# akabeacon_square_type1_MDBT40.net
KiCad netlist of a schematic drawn in EAGLE
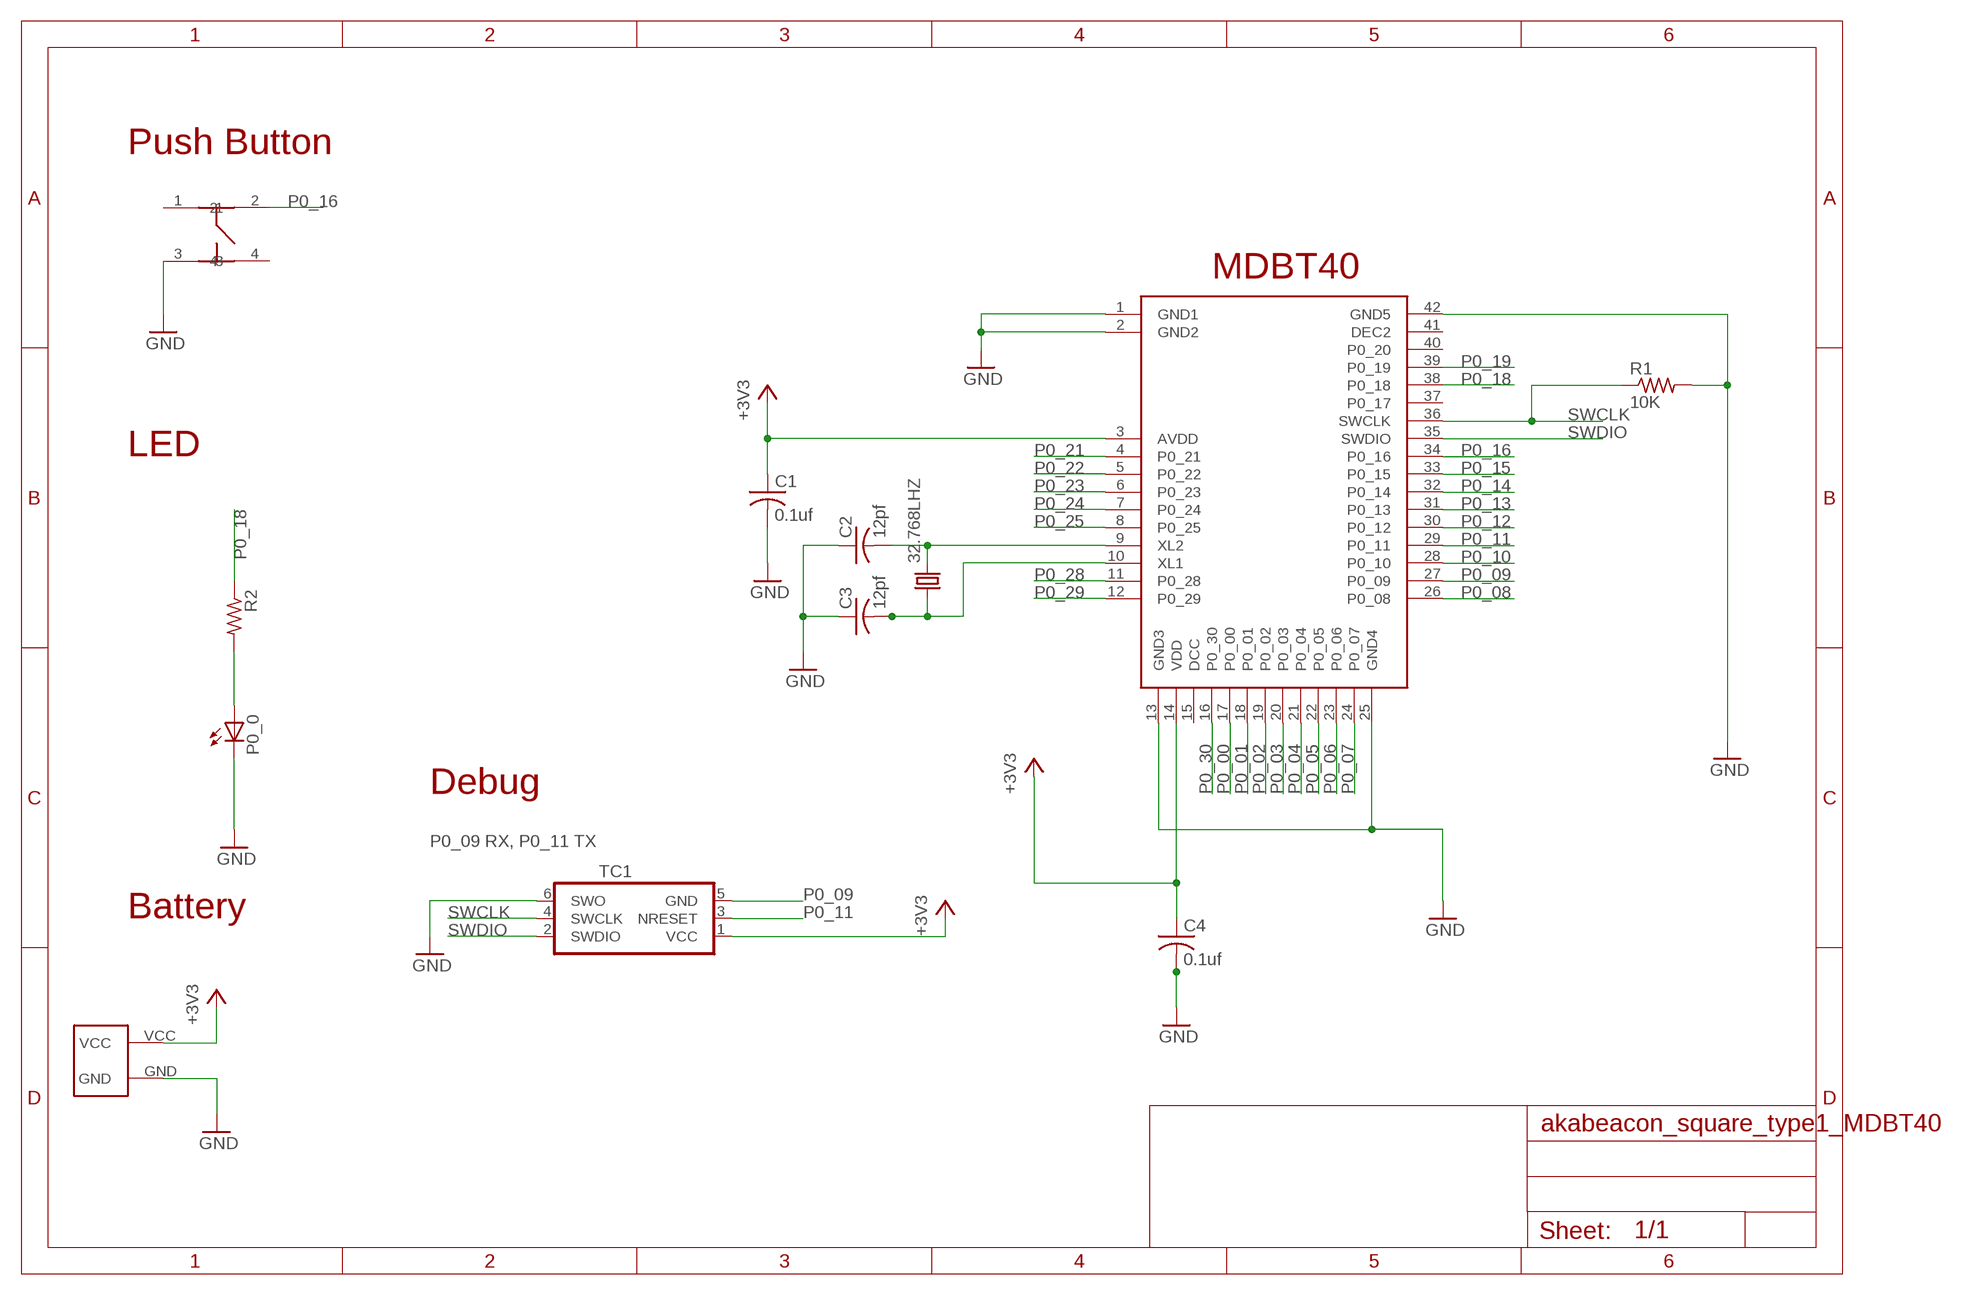
[diagram p0: schematic, sheet 1]

(export (version "E")
  (design (tool "Eeschema 10.0.6"))
  (components
    (comp (ref "32.768LHZ")
      (value "FC-12M")
      (footprint "eagle-import:FC-12M")
      (libsource (lib "eagle-import") (part "FC-12M"))
    )
    (comp (ref "C1")
      (value "0.1uf")
      (footprint "eagle-import:C0603")
      (libsource (lib "eagle-import") (part "C-USC0603"))
    )
    (comp (ref "C2")
      (value "12pf")
      (footprint "eagle-import:C0603")
      (libsource (lib "eagle-import") (part "C-USC0603"))
    )
    (comp (ref "C3")
      (value "12pf")
      (footprint "eagle-import:C0603")
      (libsource (lib "eagle-import") (part "C-USC0603"))
    )
    (comp (ref "C4")
      (value "0.1uf")
      (footprint "eagle-import:C0603")
      (libsource (lib "eagle-import") (part "C-USC0603"))
    )
    (comp (ref "P0_0")
      (value "LEDCHIP-LED0603")
      (footprint "eagle-import:CHIP-LED0603")
      (libsource (lib "eagle-import") (part "LEDCHIP-LED0603"))
    )
    (comp (ref "R1")
      (value "10K")
      (footprint "eagle-import:R0603")
      (libsource (lib "eagle-import") (part "R-US_R0603"))
    )
    (comp (ref "R2")
      (value "R-US_R0603")
      (footprint "eagle-import:R0603")
      (libsource (lib "eagle-import") (part "R-US_R0603"))
    )
    (comp (ref "TC1")
      (value "TC2030-IDC-NL")
      (footprint "eagle-import:TC2030-IDC-NL")
      (libsource (lib "eagle-import") (part "TC2030-IDC-NL"))
    )
    (comp (ref "U$2")
      (value "SQUARE-TYPE1")
      (footprint "eagle-import:SQUARE-TYPE1-TC2030")
      (libsource (lib "eagle-import") (part "SQUARE-TYPE1"))
    )
    (comp (ref "U$3")
      (value "RAYTAC-MDBT40")
      (footprint "eagle-import:RAYTAC-MDBT40")
      (libsource (lib "eagle-import") (part "RAYTAC-MDBT40"))
    )
    (comp (ref "U$6")
      (value "SWICTH-4P(KMR2)")
      (footprint "eagle-import:SWITCH-4P(KMR2)")
      (libsource (lib "eagle-import") (part "SWICTH-4P(KMR2)"))
    )
  )
  (nets
    (net (code "1") (name "+3V3") (class "Default")
      (node (ref "C1") (pin "1") (pinfunction "1_1") (pintype "passive"))
      (node (ref "C4") (pin "1") (pinfunction "1_1") (pintype "passive"))
      (node (ref "TC1") (pin "1") (pinfunction "VCC_1") (pintype "passive"))
      (node (ref "U$2") (pin "VCC") (pinfunction "VCC_VCC") (pintype "bidirectional"))
      (node (ref "U$3") (pin "14") (pinfunction "VDD_14") (pintype "bidirectional"))
      (node (ref "U$3") (pin "3") (pinfunction "AVDD_3") (pintype "bidirectional"))
    )
    (net (code "2") (name "/P0_00") (class "Default")
      (node (ref "U$3") (pin "17") (pinfunction "P0_00_17") (pintype "bidirectional"))
    )
    (net (code "3") (name "/P0_01") (class "Default")
      (node (ref "U$3") (pin "18") (pinfunction "P0_01_18") (pintype "bidirectional"))
    )
    (net (code "4") (name "/P0_02") (class "Default")
      (node (ref "U$3") (pin "19") (pinfunction "P0_02_19") (pintype "bidirectional"))
    )
    (net (code "5") (name "/P0_03") (class "Default")
      (node (ref "U$3") (pin "20") (pinfunction "P0_03_20") (pintype "bidirectional"))
    )
    (net (code "6") (name "/P0_04") (class "Default")
      (node (ref "U$3") (pin "21") (pinfunction "P0_04_21") (pintype "bidirectional"))
    )
    (net (code "7") (name "/P0_05") (class "Default")
      (node (ref "U$3") (pin "22") (pinfunction "P0_05_22") (pintype "bidirectional"))
    )
    (net (code "8") (name "/P0_06") (class "Default")
      (node (ref "U$3") (pin "23") (pinfunction "P0_06_23") (pintype "bidirectional"))
    )
    (net (code "9") (name "/P0_07") (class "Default")
      (node (ref "U$3") (pin "24") (pinfunction "P0_07_24") (pintype "bidirectional"))
    )
    (net (code "10") (name "/P0_08") (class "Default")
      (node (ref "U$3") (pin "26") (pinfunction "P0_08_26") (pintype "bidirectional"))
    )
    (net (code "11") (name "/P0_09") (class "Default")
      (node (ref "TC1") (pin "5") (pinfunction "GND_5") (pintype "passive"))
      (node (ref "U$3") (pin "27") (pinfunction "P0_09_27") (pintype "bidirectional"))
    )
    (net (code "12") (name "/P0_10") (class "Default")
      (node (ref "U$3") (pin "28") (pinfunction "P0_10_28") (pintype "bidirectional"))
    )
    (net (code "13") (name "/P0_11") (class "Default")
      (node (ref "TC1") (pin "3") (pinfunction "NRESET_3") (pintype "passive"))
      (node (ref "U$3") (pin "29") (pinfunction "P0_11_29") (pintype "bidirectional"))
    )
    (net (code "14") (name "/P0_12") (class "Default")
      (node (ref "U$3") (pin "30") (pinfunction "P0_12_30") (pintype "bidirectional"))
    )
    (net (code "15") (name "/P0_13") (class "Default")
      (node (ref "U$3") (pin "31") (pinfunction "P0_13_31") (pintype "bidirectional"))
    )
    (net (code "16") (name "/P0_14") (class "Default")
      (node (ref "U$3") (pin "32") (pinfunction "P0_14_32") (pintype "bidirectional"))
    )
    (net (code "17") (name "/P0_15") (class "Default")
      (node (ref "U$3") (pin "33") (pinfunction "P0_15_33") (pintype "bidirectional"))
    )
    (net (code "18") (name "/P0_16") (class "Default")
      (node (ref "U$3") (pin "34") (pinfunction "P0_16_34") (pintype "bidirectional"))
      (node (ref "U$6") (pin "2") (pinfunction "2_2") (pintype "bidirectional"))
    )
    (net (code "19") (name "/P0_18") (class "Default")
      (node (ref "R2") (pin "1") (pinfunction "1_1") (pintype "passive"))
      (node (ref "U$3") (pin "38") (pinfunction "P0_18_38") (pintype "bidirectional"))
    )
    (net (code "20") (name "/P0_19") (class "Default")
      (node (ref "U$3") (pin "39") (pinfunction "P0_19_39") (pintype "bidirectional"))
    )
    (net (code "21") (name "/P0_21") (class "Default")
      (node (ref "U$3") (pin "4") (pinfunction "P0_21_4") (pintype "bidirectional"))
    )
    (net (code "22") (name "/P0_22") (class "Default")
      (node (ref "U$3") (pin "5") (pinfunction "P0_22_5") (pintype "bidirectional"))
    )
    (net (code "23") (name "/P0_23") (class "Default")
      (node (ref "U$3") (pin "6") (pinfunction "P0_23_6") (pintype "bidirectional"))
    )
    (net (code "24") (name "/P0_24") (class "Default")
      (node (ref "U$3") (pin "7") (pinfunction "P0_24_7") (pintype "bidirectional"))
    )
    (net (code "25") (name "/P0_25") (class "Default")
      (node (ref "U$3") (pin "8") (pinfunction "P0_25_8") (pintype "bidirectional"))
    )
    (net (code "26") (name "/P0_28") (class "Default")
      (node (ref "U$3") (pin "11") (pinfunction "P0_28_11") (pintype "bidirectional"))
    )
    (net (code "27") (name "/P0_29") (class "Default")
      (node (ref "U$3") (pin "12") (pinfunction "P0_29_12") (pintype "bidirectional"))
    )
    (net (code "28") (name "/P0_30") (class "Default")
      (node (ref "U$3") (pin "16") (pinfunction "P0_30_16") (pintype "bidirectional"))
    )
    (net (code "29") (name "/SWCLK") (class "Default")
      (node (ref "R1") (pin "1") (pinfunction "1_1") (pintype "passive"))
      (node (ref "TC1") (pin "4") (pinfunction "SWCLK_4") (pintype "passive"))
      (node (ref "U$3") (pin "36") (pinfunction "SWCLK_36") (pintype "bidirectional"))
    )
    (net (code "30") (name "/SWDIO") (class "Default")
      (node (ref "TC1") (pin "2") (pinfunction "SWDIO_2") (pintype "passive"))
      (node (ref "U$3") (pin "35") (pinfunction "SWDIO_35") (pintype "bidirectional"))
    )
    (net (code "31") (name "GND") (class "Default")
      (node (ref "C1") (pin "2") (pinfunction "2_2") (pintype "passive"))
      (node (ref "C2") (pin "1") (pinfunction "1_1") (pintype "passive"))
      (node (ref "C3") (pin "1") (pinfunction "1_1") (pintype "passive"))
      (node (ref "C4") (pin "2") (pinfunction "2_2") (pintype "passive"))
      (node (ref "P0_0") (pin "C") (pinfunction "C_C") (pintype "passive"))
      (node (ref "R1") (pin "2") (pinfunction "2_2") (pintype "passive"))
      (node (ref "TC1") (pin "6") (pinfunction "SWO_6") (pintype "passive"))
      (node (ref "U$2") (pin "GND") (pinfunction "GND_GND") (pintype "bidirectional"))
      (node (ref "U$3") (pin "1") (pinfunction "GND1_1") (pintype "bidirectional"))
      (node (ref "U$3") (pin "13") (pinfunction "GND3_13") (pintype "bidirectional"))
      (node (ref "U$3") (pin "2") (pinfunction "GND2_2") (pintype "bidirectional"))
      (node (ref "U$3") (pin "25") (pinfunction "GND4_25") (pintype "bidirectional"))
      (node (ref "U$3") (pin "42") (pinfunction "GND5_42") (pintype "bidirectional"))
      (node (ref "U$6") (pin "3") (pinfunction "3_3") (pintype "bidirectional"))
    )
    (net (code "32") (name "Net-(P0_0-PadA)") (class "Default")
      (node (ref "P0_0") (pin "A") (pinfunction "A_A") (pintype "passive"))
      (node (ref "R2") (pin "2") (pinfunction "2_2") (pintype "passive"))
    )
    (net (code "33") (name "Net-(U$3-XL1)") (class "Default")
      (node (ref "32.768LHZ") (pin "1") (pinfunction "1_1") (pintype "passive"))
      (node (ref "C3") (pin "2") (pinfunction "2_2") (pintype "passive"))
      (node (ref "U$3") (pin "10") (pinfunction "XL1_10") (pintype "bidirectional"))
    )
    (net (code "34") (name "Net-(U$3-XL2)") (class "Default")
      (node (ref "32.768LHZ") (pin "2") (pinfunction "2_2") (pintype "passive"))
      (node (ref "C2") (pin "2") (pinfunction "2_2") (pintype "passive"))
      (node (ref "U$3") (pin "9") (pinfunction "XL2_9") (pintype "bidirectional"))
    )
    (net (code "35") (name "unconnected-(U$3-DCC-Pad15)") (class "Default")
      (node (ref "U$3") (pin "15") (pinfunction "DCC_15") (pintype "bidirectional"))
    )
    (net (code "36") (name "unconnected-(U$3-DEC2-Pad41)") (class "Default")
      (node (ref "U$3") (pin "41") (pinfunction "DEC2_41") (pintype "bidirectional"))
    )
    (net (code "37") (name "unconnected-(U$3-P0_17-Pad37)") (class "Default")
      (node (ref "U$3") (pin "37") (pinfunction "P0_17_37") (pintype "bidirectional"))
    )
    (net (code "38") (name "unconnected-(U$3-P0_20-Pad40)") (class "Default")
      (node (ref "U$3") (pin "40") (pinfunction "P0_20_40") (pintype "bidirectional"))
    )
    (net (code "39") (name "unconnected-(U$6-Pad1)") (class "Default")
      (node (ref "U$6") (pin "1") (pinfunction "1_1") (pintype "bidirectional"))
    )
    (net (code "40") (name "unconnected-(U$6-Pad4)") (class "Default")
      (node (ref "U$6") (pin "4") (pinfunction "4_4") (pintype "bidirectional"))
    )
  )
)
